# 07sdcard.net
KiCad netlist of a schematic drawn in Altium Designer
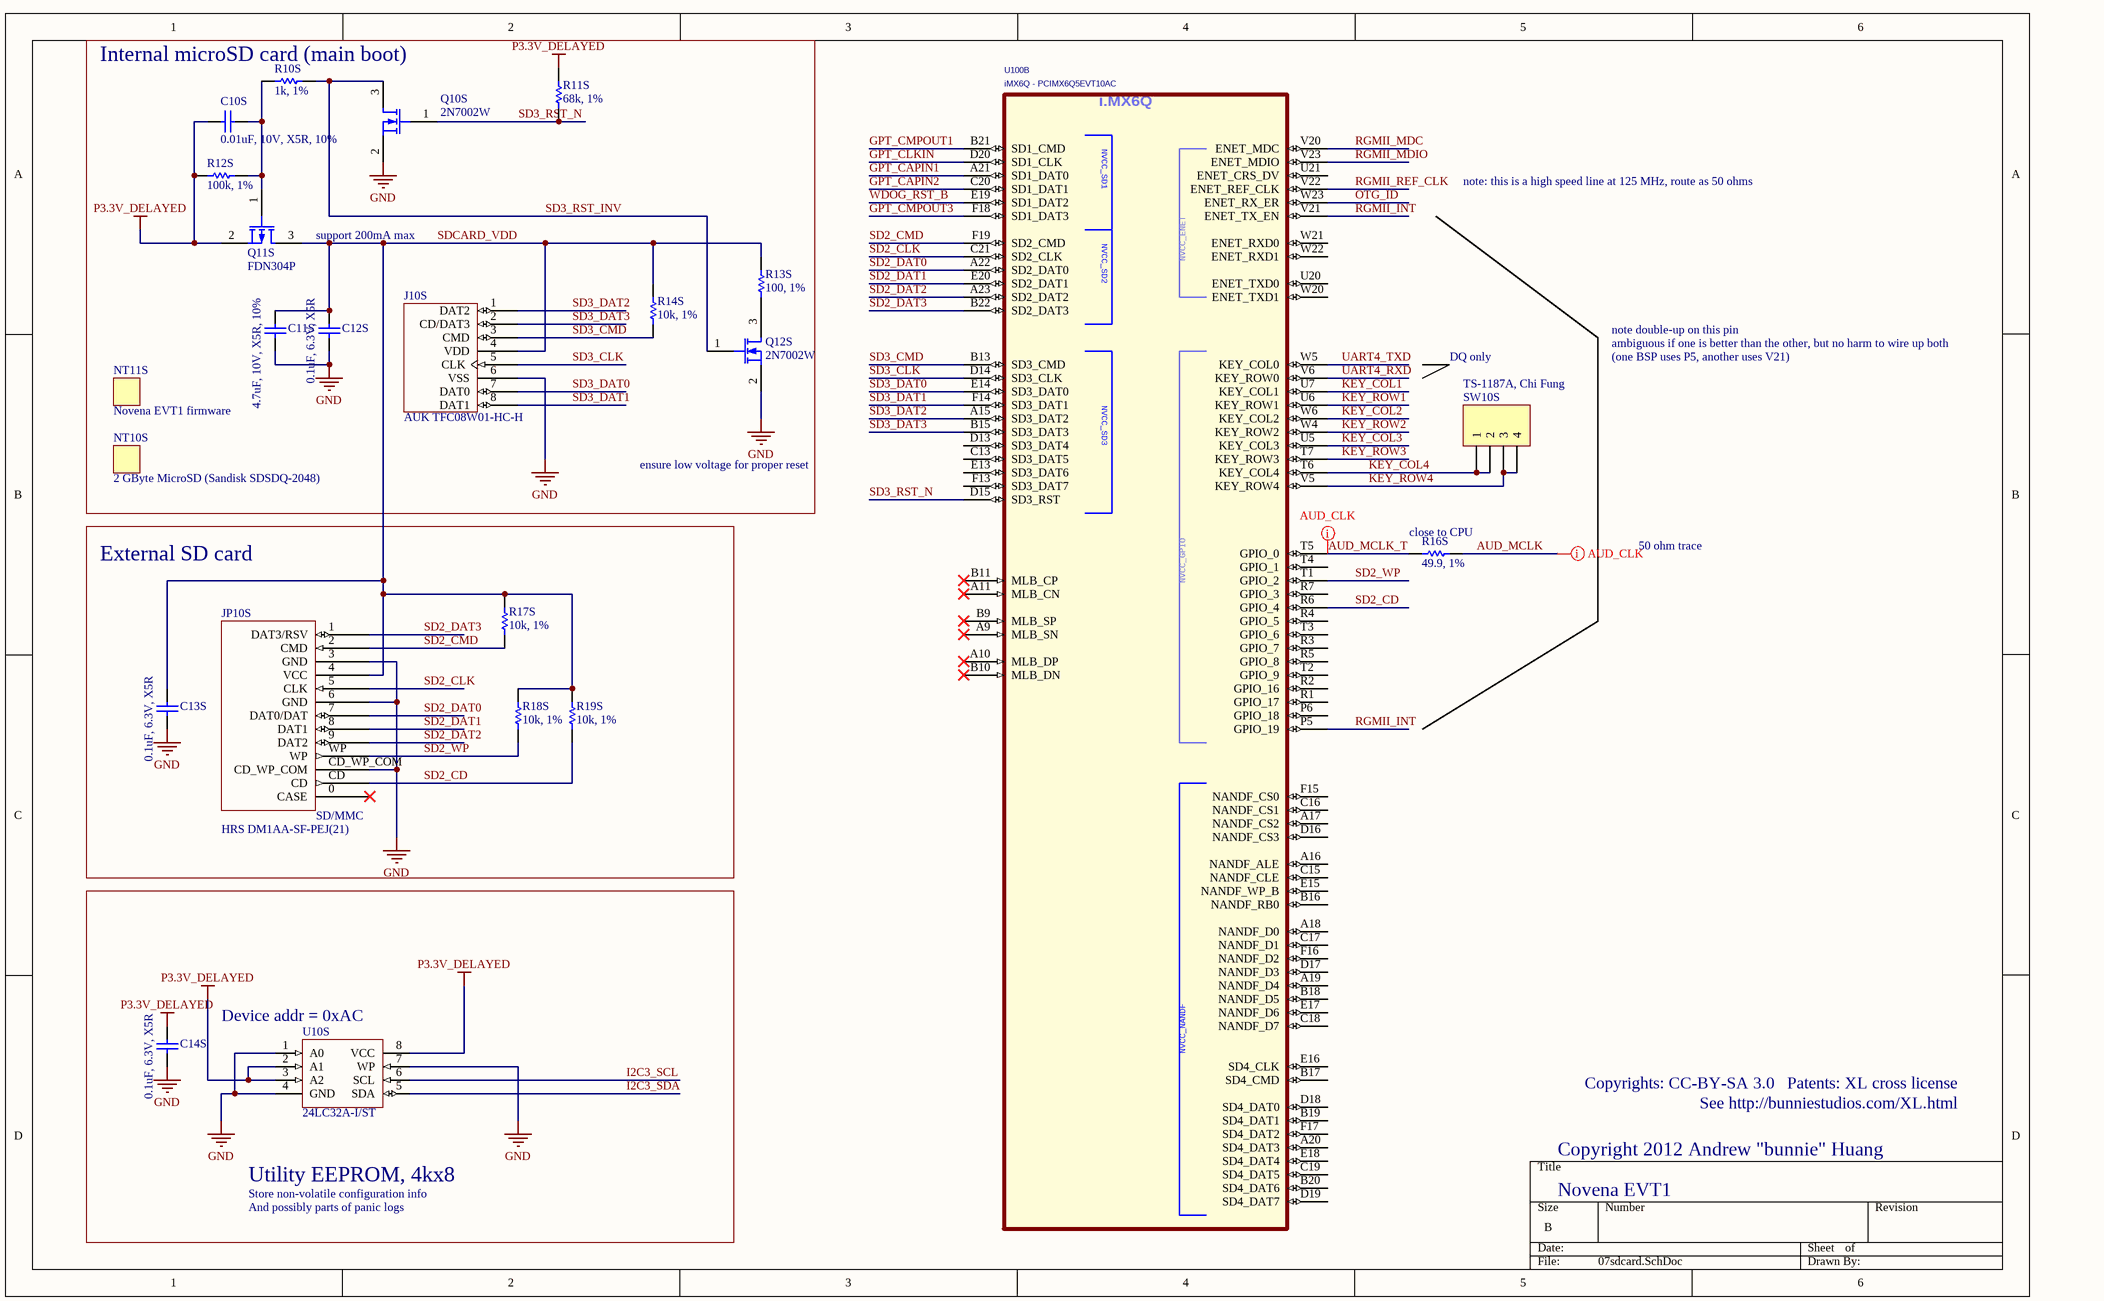
[diagram p0: 07sdcard.SchDoc]

(export (version "E")
  (design (tool "Eeschema 10.0.6"))
  (components
    (comp (ref "C10S")
      (value "0.01uF, 10V, X5R, 10%")
      (footprint "CAPC0603N_B")
      (description "Capacitor (Semiconductor SIM Model)")
      (fields (field (name "PUBLISHER") "Altium Limited"))
      (libsource (lib "Miscellaneous Devices") (part "Cap Semi"))
    )
    (comp (ref "C11S")
      (value "4.7uF, 10V, X5R, 10%")
      (footprint "CAPC1608N")
      (description "Capacitor (Semiconductor SIM Model)")
      (fields (field (name "PUBLISHER") "Altium Limited"))
      (libsource (lib "Miscellaneous Devices") (part "Cap Semi"))
    )
    (comp (ref "C12S")
      (value "0.1uF, 6.3V, X5R")
      (footprint "CAPC0603N_B")
      (description "Capacitor (Semiconductor SIM Model)")
      (fields (field (name "PUBLISHER") "Altium Limited"))
      (libsource (lib "Miscellaneous Devices") (part "Cap Semi"))
    )
    (comp (ref "C13S")
      (value "0.1uF, 6.3V, X5R")
      (footprint "CAPC0603N_B")
      (description "Capacitor (Semiconductor SIM Model)")
      (fields (field (name "PUBLISHER") "Altium Limited"))
      (libsource (lib "Miscellaneous Devices") (part "Cap Semi"))
    )
    (comp (ref "C14S")
      (value "0.1uF, 6.3V, X5R")
      (footprint "CAPC0603N_B")
      (description "Capacitor (Semiconductor SIM Model)")
      (fields (field (name "PUBLISHER") "Altium Limited"))
      (libsource (lib "Miscellaneous Devices") (part "Cap Semi"))
    )
    (comp (ref "J10S")
      (value "AUK TFC08W01-HC-H")
      (footprint "AUK_TFC08W01-HC-H")
      (description "Captive Micro-SD card for firmware images")
      (libsource (lib "commonsch") (part "MICRO_SD"))
    )
    (comp (ref "JP10S")
      (value "HRS DM1AA-SF-PEJ(21)")
      (footprint "HRS_DM1AA_SF_PEJ(21)")
      (description "SD card connector")
      (libsource (lib "commonsch") (part "HRS_DM1AA_SF_PEJ(21)"))
    )
    (comp (ref "NT10S")
      (value "2 GByte MicroSD (Sandisk SDSDQ-2048)")
      (description "Placeholder for non-electrical BOM items")
      (libsource (lib "commonsch") (part "NOTE"))
    )
    (comp (ref "NT11S")
      (value "Novena EVT1 firmware")
      (description "Placeholder for non-electrical BOM items")
      (libsource (lib "commonsch") (part "NOTE"))
    )
    (comp (ref "Q10S")
      (value "2N7002W")
      (footprint "SOT323-3AN")
      (description "N-Channel MOSFET")
      (fields (field (name "PUBLISHER") "Altium Limited"))
      (libsource (lib "Miscellaneous Devices") (part "MOSFET-N"))
    )
    (comp (ref "Q11S")
      (value "FDN304P")
      (footprint "SOT23-3N")
      (description "P-Channel MOSFET")
      (fields (field (name "PUBLISHER") "Altium Limited"))
      (libsource (lib "Miscellaneous Devices") (part "MOSFET-P"))
    )
    (comp (ref "Q12S")
      (value "2N7002W")
      (footprint "SOT323-3AN")
      (description "N-Channel MOSFET")
      (fields (field (name "PUBLISHER") "Altium Limited"))
      (libsource (lib "Miscellaneous Devices") (part "MOSFET-N"))
    )
    (comp (ref "R10S")
      (value "1k, 1%")
      (footprint "RESC1005N")
      (description "Resistor")
      (fields (field (name "PUBLISHER") "Altium Limited"))
      (libsource (lib "Miscellaneous Devices") (part "Res1"))
    )
    (comp (ref "R11S")
      (value "68k, 1%")
      (footprint "RESC1005N")
      (description "Resistor")
      (fields (field (name "PUBLISHER") "Altium Limited"))
      (libsource (lib "Miscellaneous Devices") (part "Res1"))
    )
    (comp (ref "R12S")
      (value "100k, 1%")
      (footprint "RESC1005N")
      (description "Resistor")
      (fields (field (name "PUBLISHER") "Altium Limited"))
      (libsource (lib "Miscellaneous Devices") (part "Res1"))
    )
    (comp (ref "R13S")
      (value "100, 1%")
      (footprint "RESC1005N")
      (description "Resistor")
      (fields (field (name "PUBLISHER") "Altium Limited"))
      (libsource (lib "Miscellaneous Devices") (part "Res1"))
    )
    (comp (ref "R14S")
      (value "10k, 1%")
      (footprint "RESC1005N")
      (description "Resistor")
      (fields (field (name "PUBLISHER") "Altium Limited"))
      (libsource (lib "Miscellaneous Devices") (part "Res1"))
    )
    (comp (ref "R16S")
      (value "49.9, 1%")
      (footprint "RESC1005N")
      (description "Resistor")
      (fields (field (name "PUBLISHER") "Altium Limited"))
      (libsource (lib "Miscellaneous Devices") (part "Res1"))
    )
    (comp (ref "R17S")
      (value "10k, 1%")
      (footprint "RESC1005N")
      (description "Resistor")
      (fields (field (name "PUBLISHER") "Altium Limited"))
      (libsource (lib "Miscellaneous Devices") (part "Res1"))
    )
    (comp (ref "R18S")
      (value "10k, 1%")
      (footprint "RESC1005N")
      (description "Resistor")
      (fields (field (name "PUBLISHER") "Altium Limited"))
      (libsource (lib "Miscellaneous Devices") (part "Res1"))
    )
    (comp (ref "R19S")
      (value "10k, 1%")
      (footprint "RESC1005N")
      (description "Resistor")
      (fields (field (name "PUBLISHER") "Altium Limited"))
      (libsource (lib "Miscellaneous Devices") (part "Res1"))
    )
    (comp (ref "SW10S")
      (value "TS-1187A, Chi Fung")
      (footprint "SWITCH_TS-1187A")
      (description "Chi Fung TS-1187A")
      (fields (field (name "PUBLISHER") "Altium Limited"))
      (libsource (lib "Miscellaneous Connectors") (part "Header 4"))
    )
    (comp (ref "U10S")
      (value "24LC32A-I/ST")
      (footprint "TSOP65P640-8AN")
      (description "8kbit (1kx8) I2C EEPROM")
      (libsource (lib "*") (part "AT24C08"))
    )
    (comp (ref "U100")
      (value "iMX6Q - PCIMX6Q5EVT10AC")
      (description "PLACEHOLDER FOR FREESCALE PART NUMBER PMCIMX6Q6VV1A.")
      (libsource (lib "*") (part "PCIMX6Q6VV1A"))
    )
  )
  (nets
    (net (code "1") (name "/AUD_MCLK") (class "Default")
      (node (ref "R16S") (pin "1") (pinfunction "1_1") (pintype "passive"))
    )
    (net (code "2") (name "/AUD_MCLK_T") (class "Default")
      (node (ref "R16S") (pin "2") (pinfunction "2_2") (pintype "passive"))
      (node (ref "U100") (pin "T5") (pinfunction "GPIO_0_T5") (pintype "bidirectional"))
    )
    (net (code "3") (name "/GPT_CAPIN1") (class "Default")
      (node (ref "U100") (pin "A21") (pinfunction "SD1_DAT0_A21") (pintype "bidirectional"))
    )
    (net (code "4") (name "/GPT_CAPIN2") (class "Default")
      (node (ref "U100") (pin "C20") (pinfunction "SD1_DAT1_C20") (pintype "bidirectional"))
    )
    (net (code "5") (name "/GPT_CLKIN") (class "Default")
      (node (ref "U100") (pin "D20") (pinfunction "SD1_CLK_D20") (pintype "bidirectional"))
    )
    (net (code "6") (name "/GPT_CMPOUT1") (class "Default")
      (node (ref "U100") (pin "B21") (pinfunction "SD1_CMD_B21") (pintype "bidirectional"))
    )
    (net (code "7") (name "/GPT_CMPOUT3") (class "Default")
      (node (ref "U100") (pin "F18") (pinfunction "SD1_DAT3_F18") (pintype "bidirectional"))
    )
    (net (code "8") (name "/I2C3_SCL") (class "Default")
      (node (ref "U10S") (pin "6") (pinfunction "SCL_6") (pintype "input"))
    )
    (net (code "9") (name "/I2C3_SDA") (class "Default")
      (node (ref "U10S") (pin "5") (pinfunction "SDA_5") (pintype "bidirectional"))
    )
    (net (code "10") (name "/KEY_COL1") (class "Default")
      (node (ref "U100") (pin "U7") (pinfunction "KEY_COL1_U7") (pintype "bidirectional"))
    )
    (net (code "11") (name "/KEY_COL2") (class "Default")
      (node (ref "U100") (pin "W6") (pinfunction "KEY_COL2_W6") (pintype "bidirectional"))
    )
    (net (code "12") (name "/KEY_COL3") (class "Default")
      (node (ref "U100") (pin "U5") (pinfunction "KEY_COL3_U5") (pintype "bidirectional"))
    )
    (net (code "13") (name "/KEY_COL4") (class "Default")
      (node (ref "SW10S") (pin "1") (pinfunction "1_1") (pintype "passive"))
      (node (ref "SW10S") (pin "2") (pinfunction "2_2") (pintype "passive"))
      (node (ref "U100") (pin "T6") (pinfunction "KEY_COL4_T6") (pintype "bidirectional"))
    )
    (net (code "14") (name "/KEY_ROW1") (class "Default")
      (node (ref "U100") (pin "U6") (pinfunction "KEY_ROW1_U6") (pintype "bidirectional"))
    )
    (net (code "15") (name "/KEY_ROW2") (class "Default")
      (node (ref "U100") (pin "W4") (pinfunction "KEY_ROW2_W4") (pintype "bidirectional"))
    )
    (net (code "16") (name "/KEY_ROW3") (class "Default")
      (node (ref "U100") (pin "T7") (pinfunction "KEY_ROW3_T7") (pintype "bidirectional"))
    )
    (net (code "17") (name "/KEY_ROW4") (class "Default")
      (node (ref "SW10S") (pin "3") (pinfunction "3_3") (pintype "passive"))
      (node (ref "SW10S") (pin "4") (pinfunction "4_4") (pintype "passive"))
      (node (ref "U100") (pin "V5") (pinfunction "KEY_ROW4_V5") (pintype "bidirectional"))
    )
    (net (code "18") (name "/OTG_ID") (class "Default")
      (node (ref "U100") (pin "W23") (pinfunction "ENET_RX_ER_W23") (pintype "bidirectional"))
    )
    (net (code "19") (name "/RGMII_INT") (class "Default")
      (node (ref "U100") (pin "P5") (pinfunction "GPIO_19_P5") (pintype "bidirectional"))
      (node (ref "U100") (pin "V21") (pinfunction "ENET_TX_EN_V21") (pintype "bidirectional"))
    )
    (net (code "20") (name "/RGMII_MDC") (class "Default")
      (node (ref "U100") (pin "V20") (pinfunction "ENET_MDC_V20") (pintype "bidirectional"))
    )
    (net (code "21") (name "/RGMII_MDIO") (class "Default")
      (node (ref "U100") (pin "V23") (pinfunction "ENET_MDIO_V23") (pintype "bidirectional"))
    )
    (net (code "22") (name "/RGMII_REF_CLK") (class "Default")
      (node (ref "U100") (pin "V22") (pinfunction "ENET_REF_CLK_V22") (pintype "bidirectional"))
    )
    (net (code "23") (name "/SD2_CD") (class "Default")
      (node (ref "JP10S") (pin "CD") (pinfunction "CD_CD") (pintype "output"))
      (node (ref "R19S") (pin "2") (pinfunction "2_2") (pintype "passive"))
      (node (ref "U100") (pin "R6") (pinfunction "GPIO_4_R6") (pintype "bidirectional"))
    )
    (net (code "24") (name "/SD2_CLK") (class "Default")
      (node (ref "JP10S") (pin "5") (pinfunction "CLK_5") (pintype "input"))
      (node (ref "U100") (pin "C21") (pinfunction "SD2_CLK_C21") (pintype "bidirectional"))
    )
    (net (code "25") (name "/SD2_CMD") (class "Default")
      (node (ref "JP10S") (pin "2") (pinfunction "CMD_2") (pintype "input"))
      (node (ref "R17S") (pin "2") (pinfunction "2_2") (pintype "passive"))
      (node (ref "U100") (pin "F19") (pinfunction "SD2_CMD_F19") (pintype "bidirectional"))
    )
    (net (code "26") (name "/SD2_DAT0") (class "Default")
      (node (ref "JP10S") (pin "7") (pinfunction "DAT0/DAT_7") (pintype "bidirectional"))
      (node (ref "U100") (pin "A22") (pinfunction "SD2_DAT0_A22") (pintype "bidirectional"))
    )
    (net (code "27") (name "/SD2_DAT1") (class "Default")
      (node (ref "JP10S") (pin "8") (pinfunction "DAT1_8") (pintype "bidirectional"))
      (node (ref "U100") (pin "E20") (pinfunction "SD2_DAT1_E20") (pintype "bidirectional"))
    )
    (net (code "28") (name "/SD2_DAT2") (class "Default")
      (node (ref "JP10S") (pin "9") (pinfunction "DAT2_9") (pintype "bidirectional"))
      (node (ref "U100") (pin "A23") (pinfunction "SD2_DAT2_A23") (pintype "bidirectional"))
    )
    (net (code "29") (name "/SD2_DAT3") (class "Default")
      (node (ref "JP10S") (pin "1") (pinfunction "DAT3/RSV_1") (pintype "bidirectional"))
      (node (ref "U100") (pin "B22") (pinfunction "SD2_DAT3_B22") (pintype "bidirectional"))
    )
    (net (code "30") (name "/SD2_WP") (class "Default")
      (node (ref "JP10S") (pin "WP") (pinfunction "WP_WP") (pintype "output"))
      (node (ref "R18S") (pin "2") (pinfunction "2_2") (pintype "passive"))
      (node (ref "U100") (pin "T1") (pinfunction "GPIO_2_T1") (pintype "bidirectional"))
    )
    (net (code "31") (name "/SD3_CLK") (class "Default")
      (node (ref "J10S") (pin "5") (pinfunction "CLK_5") (pintype "input"))
      (node (ref "U100") (pin "D14") (pinfunction "SD3_CLK_D14") (pintype "bidirectional"))
    )
    (net (code "32") (name "/SD3_CMD") (class "Default")
      (node (ref "J10S") (pin "3") (pinfunction "CMD_3") (pintype "bidirectional"))
      (node (ref "R14S") (pin "2") (pinfunction "2_2") (pintype "passive"))
      (node (ref "U100") (pin "B13") (pinfunction "SD3_CMD_B13") (pintype "bidirectional"))
    )
    (net (code "33") (name "/SD3_DAT0") (class "Default")
      (node (ref "J10S") (pin "7") (pinfunction "DAT0_7") (pintype "bidirectional"))
      (node (ref "U100") (pin "E14") (pinfunction "SD3_DAT0_E14") (pintype "bidirectional"))
    )
    (net (code "34") (name "/SD3_DAT1") (class "Default")
      (node (ref "J10S") (pin "8") (pinfunction "DAT1_8") (pintype "bidirectional"))
      (node (ref "U100") (pin "F14") (pinfunction "SD3_DAT1_F14") (pintype "bidirectional"))
    )
    (net (code "35") (name "/SD3_DAT2") (class "Default")
      (node (ref "J10S") (pin "1") (pinfunction "DAT2_1") (pintype "bidirectional"))
      (node (ref "U100") (pin "A15") (pinfunction "SD3_DAT2_A15") (pintype "bidirectional"))
    )
    (net (code "36") (name "/SD3_DAT3") (class "Default")
      (node (ref "J10S") (pin "2") (pinfunction "CD/DAT3_2") (pintype "bidirectional"))
      (node (ref "U100") (pin "B15") (pinfunction "SD3_DAT3_B15") (pintype "bidirectional"))
    )
    (net (code "37") (name "/SD3_RST_INV") (class "Default")
      (node (ref "Q10S") (pin "3") (pinfunction "D_3") (pintype "passive"))
      (node (ref "Q12S") (pin "1") (pinfunction "G_1") (pintype "passive"))
      (node (ref "R10S") (pin "1") (pinfunction "1_1") (pintype "passive"))
    )
    (net (code "38") (name "/SD3_RST_N") (class "Default")
      (node (ref "Q10S") (pin "1") (pinfunction "G_1") (pintype "passive"))
      (node (ref "R11S") (pin "2") (pinfunction "2_2") (pintype "passive"))
      (node (ref "U100") (pin "D15") (pinfunction "SD3_RST_D15") (pintype "bidirectional"))
    )
    (net (code "39") (name "/SDCARD_VDD") (class "Default")
      (node (ref "C11S") (pin "1") (pinfunction "1_1") (pintype "passive"))
      (node (ref "C12S") (pin "1") (pinfunction "1_1") (pintype "passive"))
      (node (ref "C13S") (pin "1") (pinfunction "1_1") (pintype "passive"))
      (node (ref "J10S") (pin "4") (pinfunction "VDD_4") (pintype "power_in"))
      (node (ref "JP10S") (pin "4") (pinfunction "VCC_4") (pintype "power_in"))
      (node (ref "Q11S") (pin "3") (pinfunction "D_3") (pintype "passive"))
      (node (ref "R13S") (pin "1") (pinfunction "1_1") (pintype "passive"))
      (node (ref "R14S") (pin "1") (pinfunction "1_1") (pintype "passive"))
      (node (ref "R17S") (pin "1") (pinfunction "1_1") (pintype "passive"))
      (node (ref "R18S") (pin "1") (pinfunction "1_1") (pintype "passive"))
      (node (ref "R19S") (pin "1") (pinfunction "1_1") (pintype "passive"))
    )
    (net (code "40") (name "/UART4_RXD") (class "Default")
      (node (ref "U100") (pin "V6") (pinfunction "KEY_ROW0_V6") (pintype "bidirectional"))
    )
    (net (code "41") (name "/UART4_TXD") (class "Default")
      (node (ref "U100") (pin "W5") (pinfunction "KEY_COL0_W5") (pintype "bidirectional"))
    )
    (net (code "42") (name "/WDOG_RST_B") (class "Default")
      (node (ref "U100") (pin "E19") (pinfunction "SD1_DAT2_E19") (pintype "bidirectional"))
    )
    (net (code "43") (name "GND") (class "Default")
      (node (ref "C11S") (pin "2") (pinfunction "2_2") (pintype "passive"))
      (node (ref "C12S") (pin "2") (pinfunction "2_2") (pintype "passive"))
      (node (ref "C13S") (pin "2") (pinfunction "2_2") (pintype "passive"))
      (node (ref "C14S") (pin "2") (pinfunction "2_2") (pintype "passive"))
      (node (ref "J10S") (pin "6") (pinfunction "VSS_6") (pintype "power_in"))
      (node (ref "JP10S") (pin "3") (pinfunction "GND_3") (pintype "power_in"))
      (node (ref "JP10S") (pin "6") (pinfunction "GND_6") (pintype "power_in"))
      (node (ref "JP10S") (pin "CD_WP_COM") (pinfunction "CD_WP_COM_CD_WP_COM") (pintype "power_in"))
      (node (ref "Q10S") (pin "2") (pinfunction "S_2") (pintype "passive"))
      (node (ref "Q12S") (pin "2") (pinfunction "S_2") (pintype "passive"))
      (node (ref "U10S") (pin "1") (pinfunction "A0_1") (pintype "input"))
      (node (ref "U10S") (pin "4") (pinfunction "GND_4") (pintype "power_in"))
      (node (ref "U10S") (pin "7") (pinfunction "WP_7") (pintype "input"))
    )
    (net (code "44") (name "Net-(Q11S-G)") (class "Default")
      (node (ref "C10S") (pin "1") (pinfunction "1_1") (pintype "passive"))
      (node (ref "Q11S") (pin "1") (pinfunction "G_1") (pintype "passive"))
      (node (ref "R10S") (pin "2") (pinfunction "2_2") (pintype "passive"))
      (node (ref "R12S") (pin "1") (pinfunction "1_1") (pintype "passive"))
    )
    (net (code "45") (name "Net-(Q12S-D)") (class "Default")
      (node (ref "Q12S") (pin "3") (pinfunction "D_3") (pintype "passive"))
      (node (ref "R13S") (pin "2") (pinfunction "2_2") (pintype "passive"))
    )
    (net (code "46") (name "P3.3V_DELAYED") (class "Default")
      (node (ref "C10S") (pin "2") (pinfunction "2_2") (pintype "passive"))
      (node (ref "C14S") (pin "1") (pinfunction "1_1") (pintype "passive"))
      (node (ref "Q11S") (pin "2") (pinfunction "S_2") (pintype "passive"))
      (node (ref "R11S") (pin "1") (pinfunction "1_1") (pintype "passive"))
      (node (ref "R12S") (pin "2") (pinfunction "2_2") (pintype "passive"))
      (node (ref "U10S") (pin "2") (pinfunction "A1_2") (pintype "input"))
      (node (ref "U10S") (pin "3") (pinfunction "A2_3") (pintype "input"))
      (node (ref "U10S") (pin "8") (pinfunction "VCC_8") (pintype "power_in"))
    )
    (net (code "47") (name "unconnected-(JP10S-CASE-Pad0)") (class "Default")
      (node (ref "JP10S") (pin "0") (pinfunction "CASE_0") (pintype "power_in+no_connect"))
    )
    (net (code "48") (name "unconnected-(U100B-ENET_CRS_DV-PadU21)") (class "Default")
      (node (ref "U100") (pin "U21") (pinfunction "ENET_CRS_DV_U21") (pintype "bidirectional"))
    )
    (net (code "49") (name "unconnected-(U100B-ENET_RXD0-PadW21)") (class "Default")
      (node (ref "U100") (pin "W21") (pinfunction "ENET_RXD0_W21") (pintype "bidirectional"))
    )
    (net (code "50") (name "unconnected-(U100B-ENET_RXD1-PadW22)") (class "Default")
      (node (ref "U100") (pin "W22") (pinfunction "ENET_RXD1_W22") (pintype "bidirectional"))
    )
    (net (code "51") (name "unconnected-(U100B-ENET_TXD0-PadU20)") (class "Default")
      (node (ref "U100") (pin "U20") (pinfunction "ENET_TXD0_U20") (pintype "bidirectional"))
    )
    (net (code "52") (name "unconnected-(U100B-ENET_TXD1-PadW20)") (class "Default")
      (node (ref "U100") (pin "W20") (pinfunction "ENET_TXD1_W20") (pintype "bidirectional"))
    )
    (net (code "53") (name "unconnected-(U100B-GPIO_1-PadT4)") (class "Default")
      (node (ref "U100") (pin "T4") (pinfunction "GPIO_1_T4") (pintype "bidirectional"))
    )
    (net (code "54") (name "unconnected-(U100B-GPIO_3-PadR7)") (class "Default")
      (node (ref "U100") (pin "R7") (pinfunction "GPIO_3_R7") (pintype "bidirectional"))
    )
    (net (code "55") (name "unconnected-(U100B-GPIO_5-PadR4)") (class "Default")
      (node (ref "U100") (pin "R4") (pinfunction "GPIO_5_R4") (pintype "bidirectional"))
    )
    (net (code "56") (name "unconnected-(U100B-GPIO_6-PadT3)") (class "Default")
      (node (ref "U100") (pin "T3") (pinfunction "GPIO_6_T3") (pintype "bidirectional"))
    )
    (net (code "57") (name "unconnected-(U100B-GPIO_7-PadR3)") (class "Default")
      (node (ref "U100") (pin "R3") (pinfunction "GPIO_7_R3") (pintype "bidirectional"))
    )
    (net (code "58") (name "unconnected-(U100B-GPIO_8-PadR5)") (class "Default")
      (node (ref "U100") (pin "R5") (pinfunction "GPIO_8_R5") (pintype "bidirectional"))
    )
    (net (code "59") (name "unconnected-(U100B-GPIO_9-PadT2)") (class "Default")
      (node (ref "U100") (pin "T2") (pinfunction "GPIO_9_T2") (pintype "bidirectional"))
    )
    (net (code "60") (name "unconnected-(U100B-GPIO_16-PadR2)") (class "Default")
      (node (ref "U100") (pin "R2") (pinfunction "GPIO_16_R2") (pintype "bidirectional"))
    )
    (net (code "61") (name "unconnected-(U100B-GPIO_17-PadR1)") (class "Default")
      (node (ref "U100") (pin "R1") (pinfunction "GPIO_17_R1") (pintype "bidirectional"))
    )
    (net (code "62") (name "unconnected-(U100B-GPIO_18-PadP6)") (class "Default")
      (node (ref "U100") (pin "P6") (pinfunction "GPIO_18_P6") (pintype "bidirectional"))
    )
    (net (code "63") (name "unconnected-(U100B-MLB_CN-PadA11)") (class "Default")
      (node (ref "U100") (pin "A11") (pinfunction "MLB_CN_A11") (pintype "input+no_connect"))
    )
    (net (code "64") (name "unconnected-(U100B-MLB_CP-PadB11)") (class "Default")
      (node (ref "U100") (pin "B11") (pinfunction "MLB_CP_B11") (pintype "input+no_connect"))
    )
    (net (code "65") (name "unconnected-(U100B-MLB_DN-PadB10)") (class "Default")
      (node (ref "U100") (pin "B10") (pinfunction "MLB_DN_B10") (pintype "input+no_connect"))
    )
    (net (code "66") (name "unconnected-(U100B-MLB_DP-PadA10)") (class "Default")
      (node (ref "U100") (pin "A10") (pinfunction "MLB_DP_A10") (pintype "input+no_connect"))
    )
    (net (code "67") (name "unconnected-(U100B-MLB_SN-PadA9)") (class "Default")
      (node (ref "U100") (pin "A9") (pinfunction "MLB_SN_A9") (pintype "input+no_connect"))
    )
    (net (code "68") (name "unconnected-(U100B-MLB_SP-PadB9)") (class "Default")
      (node (ref "U100") (pin "B9") (pinfunction "MLB_SP_B9") (pintype "input+no_connect"))
    )
    (net (code "69") (name "unconnected-(U100B-NANDF_ALE-PadA16)") (class "Default")
      (node (ref "U100") (pin "A16") (pinfunction "NANDF_ALE_A16") (pintype "bidirectional"))
    )
    (net (code "70") (name "unconnected-(U100B-NANDF_CLE-PadC15)") (class "Default")
      (node (ref "U100") (pin "C15") (pinfunction "NANDF_CLE_C15") (pintype "bidirectional"))
    )
    (net (code "71") (name "unconnected-(U100B-NANDF_CS0-PadF15)") (class "Default")
      (node (ref "U100") (pin "F15") (pinfunction "NANDF_CS0_F15") (pintype "bidirectional"))
    )
    (net (code "72") (name "unconnected-(U100B-NANDF_CS1-PadC16)") (class "Default")
      (node (ref "U100") (pin "C16") (pinfunction "NANDF_CS1_C16") (pintype "bidirectional"))
    )
    (net (code "73") (name "unconnected-(U100B-NANDF_CS2-PadA17)") (class "Default")
      (node (ref "U100") (pin "A17") (pinfunction "NANDF_CS2_A17") (pintype "bidirectional"))
    )
    (net (code "74") (name "unconnected-(U100B-NANDF_CS3-PadD16)") (class "Default")
      (node (ref "U100") (pin "D16") (pinfunction "NANDF_CS3_D16") (pintype "bidirectional"))
    )
    (net (code "75") (name "unconnected-(U100B-NANDF_D0-PadA18)") (class "Default")
      (node (ref "U100") (pin "A18") (pinfunction "NANDF_D0_A18") (pintype "bidirectional"))
    )
    (net (code "76") (name "unconnected-(U100B-NANDF_D1-PadC17)") (class "Default")
      (node (ref "U100") (pin "C17") (pinfunction "NANDF_D1_C17") (pintype "bidirectional"))
    )
    (net (code "77") (name "unconnected-(U100B-NANDF_D2-PadF16)") (class "Default")
      (node (ref "U100") (pin "F16") (pinfunction "NANDF_D2_F16") (pintype "bidirectional"))
    )
    (net (code "78") (name "unconnected-(U100B-NANDF_D3-PadD17)") (class "Default")
      (node (ref "U100") (pin "D17") (pinfunction "NANDF_D3_D17") (pintype "bidirectional"))
    )
    (net (code "79") (name "unconnected-(U100B-NANDF_D4-PadA19)") (class "Default")
      (node (ref "U100") (pin "A19") (pinfunction "NANDF_D4_A19") (pintype "bidirectional"))
    )
    (net (code "80") (name "unconnected-(U100B-NANDF_D5-PadB18)") (class "Default")
      (node (ref "U100") (pin "B18") (pinfunction "NANDF_D5_B18") (pintype "bidirectional"))
    )
    (net (code "81") (name "unconnected-(U100B-NANDF_D6-PadE17)") (class "Default")
      (node (ref "U100") (pin "E17") (pinfunction "NANDF_D6_E17") (pintype "bidirectional"))
    )
    (net (code "82") (name "unconnected-(U100B-NANDF_D7-PadC18)") (class "Default")
      (node (ref "U100") (pin "C18") (pinfunction "NANDF_D7_C18") (pintype "bidirectional"))
    )
    (net (code "83") (name "unconnected-(U100B-NANDF_RB0-PadB16)") (class "Default")
      (node (ref "U100") (pin "B16") (pinfunction "NANDF_RB0_B16") (pintype "bidirectional"))
    )
    (net (code "84") (name "unconnected-(U100B-NANDF_WP_B-PadE15)") (class "Default")
      (node (ref "U100") (pin "E15") (pinfunction "NANDF_WP_B_E15") (pintype "bidirectional"))
    )
    (net (code "85") (name "unconnected-(U100B-SD3_DAT4-PadD13)") (class "Default")
      (node (ref "U100") (pin "D13") (pinfunction "SD3_DAT4_D13") (pintype "bidirectional"))
    )
    (net (code "86") (name "unconnected-(U100B-SD3_DAT5-PadC13)") (class "Default")
      (node (ref "U100") (pin "C13") (pinfunction "SD3_DAT5_C13") (pintype "bidirectional"))
    )
    (net (code "87") (name "unconnected-(U100B-SD3_DAT6-PadE13)") (class "Default")
      (node (ref "U100") (pin "E13") (pinfunction "SD3_DAT6_E13") (pintype "bidirectional"))
    )
    (net (code "88") (name "unconnected-(U100B-SD3_DAT7-PadF13)") (class "Default")
      (node (ref "U100") (pin "F13") (pinfunction "SD3_DAT7_F13") (pintype "bidirectional"))
    )
    (net (code "89") (name "unconnected-(U100B-SD4_CLK-PadE16)") (class "Default")
      (node (ref "U100") (pin "E16") (pinfunction "SD4_CLK_E16") (pintype "bidirectional"))
    )
    (net (code "90") (name "unconnected-(U100B-SD4_CMD-PadB17)") (class "Default")
      (node (ref "U100") (pin "B17") (pinfunction "SD4_CMD_B17") (pintype "bidirectional"))
    )
    (net (code "91") (name "unconnected-(U100B-SD4_DAT0-PadD18)") (class "Default")
      (node (ref "U100") (pin "D18") (pinfunction "SD4_DAT0_D18") (pintype "bidirectional"))
    )
    (net (code "92") (name "unconnected-(U100B-SD4_DAT1-PadB19)") (class "Default")
      (node (ref "U100") (pin "B19") (pinfunction "SD4_DAT1_B19") (pintype "bidirectional"))
    )
    (net (code "93") (name "unconnected-(U100B-SD4_DAT2-PadF17)") (class "Default")
      (node (ref "U100") (pin "F17") (pinfunction "SD4_DAT2_F17") (pintype "bidirectional"))
    )
    (net (code "94") (name "unconnected-(U100B-SD4_DAT3-PadA20)") (class "Default")
      (node (ref "U100") (pin "A20") (pinfunction "SD4_DAT3_A20") (pintype "bidirectional"))
    )
    (net (code "95") (name "unconnected-(U100B-SD4_DAT4-PadE18)") (class "Default")
      (node (ref "U100") (pin "E18") (pinfunction "SD4_DAT4_E18") (pintype "bidirectional"))
    )
    (net (code "96") (name "unconnected-(U100B-SD4_DAT5-PadC19)") (class "Default")
      (node (ref "U100") (pin "C19") (pinfunction "SD4_DAT5_C19") (pintype "bidirectional"))
    )
    (net (code "97") (name "unconnected-(U100B-SD4_DAT6-PadB20)") (class "Default")
      (node (ref "U100") (pin "B20") (pinfunction "SD4_DAT6_B20") (pintype "bidirectional"))
    )
    (net (code "98") (name "unconnected-(U100B-SD4_DAT7-PadD19)") (class "Default")
      (node (ref "U100") (pin "D19") (pinfunction "SD4_DAT7_D19") (pintype "bidirectional"))
    )
  )
)
